# BT10_Rev2.net
KiCad netlist of a schematic drawn in EAGLE
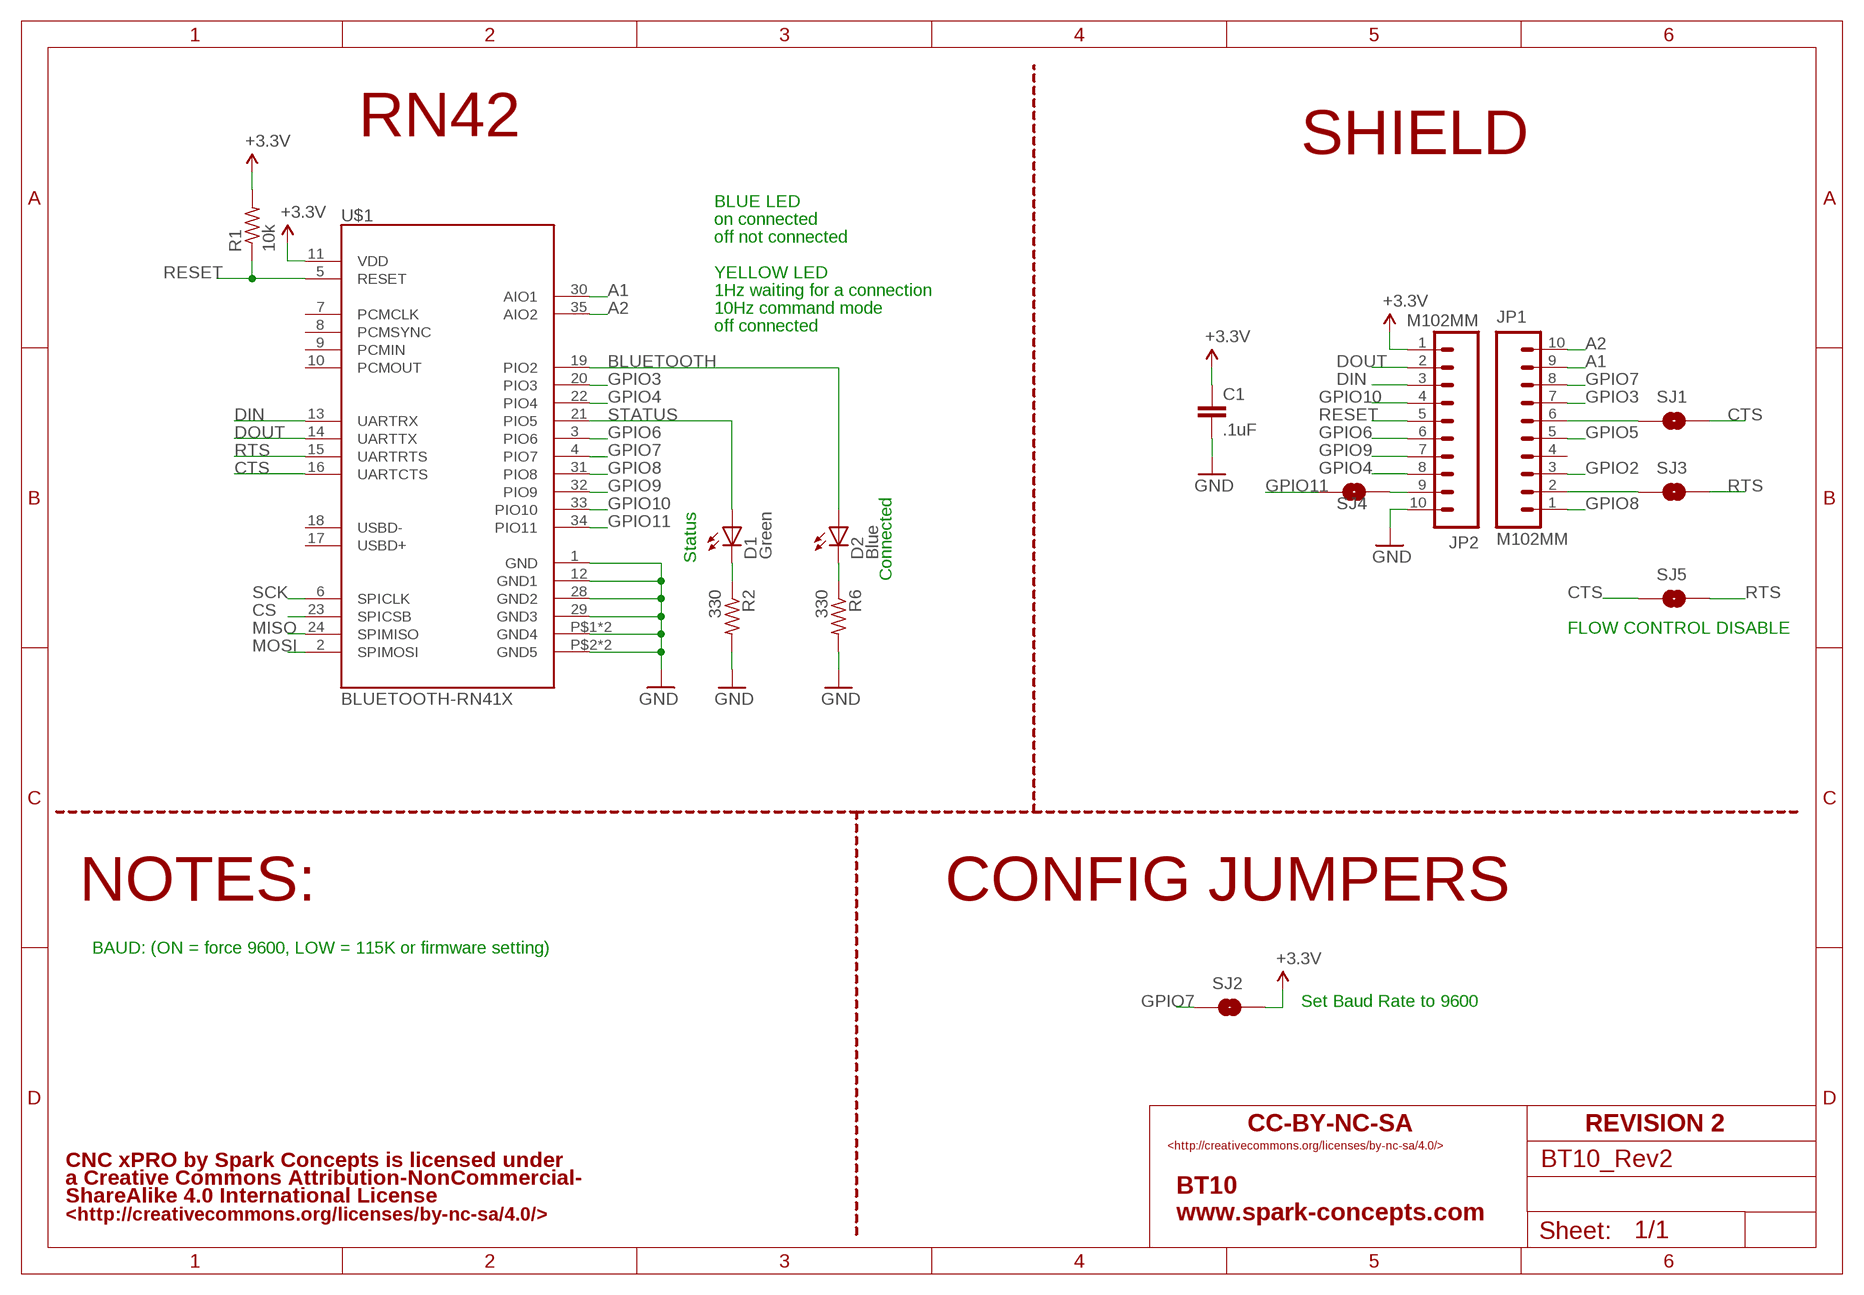
[diagram p0: schematic, sheet 1]

(export (version "E")
  (design (tool "Eeschema 10.0.6"))
  (components
    (comp (ref "C1")
      (value ".1uF")
      (footprint "eagle-import:0603-CAP")
      (libsource (lib "eagle-import") (part "CAP0603-CAP"))
    )
    (comp (ref "D1")
      (value "Green")
      (footprint "eagle-import:LED-0603")
      (libsource (lib "eagle-import") (part "LED0603"))
    )
    (comp (ref "D2")
      (value "Blue")
      (footprint "eagle-import:LED-0603")
      (libsource (lib "eagle-import") (part "LED0603"))
    )
    (comp (ref "JP1")
      (value "M102MM")
      (footprint "eagle-import:1X10-2MM")
      (libsource (lib "eagle-import") (part "M102MM"))
    )
    (comp (ref "JP2")
      (value "M102MM")
      (footprint "eagle-import:1X10-2MM")
      (libsource (lib "eagle-import") (part "M102MM"))
    )
    (comp (ref "R1")
      (value "10k")
      (footprint "eagle-import:R0603")
      (libsource (lib "eagle-import") (part "R-US_R0603"))
    )
    (comp (ref "R2")
      (value "330")
      (footprint "eagle-import:R0603")
      (libsource (lib "eagle-import") (part "R-US_R0603"))
    )
    (comp (ref "R6")
      (value "330")
      (footprint "eagle-import:R0603")
      (libsource (lib "eagle-import") (part "R-US_R0603"))
    )
    (comp (ref "SJ1")
      (value "SOLDERJUMPERNO")
      (footprint "eagle-import:SJ_2S-NO")
      (libsource (lib "eagle-import") (part "SOLDERJUMPERNO"))
    )
    (comp (ref "SJ2")
      (value "SOLDERJUMPERNC2")
      (footprint "eagle-import:SJ_2S-NOTRACE")
      (libsource (lib "eagle-import") (part "SOLDERJUMPERNC2"))
    )
    (comp (ref "SJ3")
      (value "SOLDERJUMPERNO")
      (footprint "eagle-import:SJ_2S-NO")
      (libsource (lib "eagle-import") (part "SOLDERJUMPERNO"))
    )
    (comp (ref "SJ4")
      (value "SOLDERJUMPERNO")
      (footprint "eagle-import:SJ_2S-NO")
      (libsource (lib "eagle-import") (part "SOLDERJUMPERNO"))
    )
    (comp (ref "SJ5")
      (value "SOLDERJUMPERNC2")
      (footprint "eagle-import:SJ_2S-NOTRACE")
      (libsource (lib "eagle-import") (part "SOLDERJUMPERNC2"))
    )
    (comp (ref "U$1")
      (value "BLUETOOTH-RN41X")
      (footprint "eagle-import:RN41_NO_ANT")
      (libsource (lib "eagle-import") (part "BLUETOOTH-RN41X"))
    )
  )
  (nets
    (net (code "1") (name "+3.3V") (class "Default")
      (node (ref "C1") (pin "1") (pinfunction "1_1") (pintype "passive"))
      (node (ref "JP2") (pin "1") (pinfunction "1_1") (pintype "passive"))
      (node (ref "R1") (pin "2") (pinfunction "2_2") (pintype "passive"))
      (node (ref "SJ2") (pin "2") (pinfunction "2_2") (pintype "passive"))
      (node (ref "U$1") (pin "11") (pinfunction "VDD_11") (pintype "bidirectional"))
    )
    (net (code "2") (name "/A1") (class "Default")
      (node (ref "JP1") (pin "9") (pinfunction "9_9") (pintype "passive"))
      (node (ref "U$1") (pin "30") (pinfunction "AIO1_30") (pintype "bidirectional"))
    )
    (net (code "3") (name "/A2") (class "Default")
      (node (ref "JP1") (pin "10") (pinfunction "10_10") (pintype "passive"))
      (node (ref "U$1") (pin "35") (pinfunction "AIO2_35") (pintype "bidirectional"))
    )
    (net (code "4") (name "/BLUETOOTH") (class "Default")
      (node (ref "D2") (pin "A") (pinfunction "A_A") (pintype "passive"))
      (node (ref "U$1") (pin "19") (pinfunction "PIO2_19") (pintype "bidirectional"))
    )
    (net (code "5") (name "/CS") (class "Default")
      (node (ref "U$1") (pin "23") (pinfunction "SPICSB_23") (pintype "bidirectional"))
    )
    (net (code "6") (name "/CTS") (class "Default")
      (node (ref "SJ1") (pin "2") (pinfunction "2_2") (pintype "passive"))
      (node (ref "SJ5") (pin "1") (pinfunction "1_1") (pintype "passive"))
      (node (ref "U$1") (pin "16") (pinfunction "UARTCTS_16") (pintype "bidirectional"))
    )
    (net (code "7") (name "/DIN") (class "Default")
      (node (ref "JP2") (pin "3") (pinfunction "3_3") (pintype "passive"))
      (node (ref "U$1") (pin "13") (pinfunction "UARTRX_13") (pintype "bidirectional"))
    )
    (net (code "8") (name "/DOUT") (class "Default")
      (node (ref "JP2") (pin "2") (pinfunction "2_2") (pintype "passive"))
      (node (ref "U$1") (pin "14") (pinfunction "UARTTX_14") (pintype "bidirectional"))
    )
    (net (code "9") (name "/GPIO2") (class "Default")
      (node (ref "JP1") (pin "3") (pinfunction "3_3") (pintype "passive"))
    )
    (net (code "10") (name "/GPIO3") (class "Default")
      (node (ref "JP1") (pin "7") (pinfunction "7_7") (pintype "passive"))
      (node (ref "U$1") (pin "20") (pinfunction "PIO3_20") (pintype "bidirectional"))
    )
    (net (code "11") (name "/GPIO4") (class "Default")
      (node (ref "JP2") (pin "8") (pinfunction "8_8") (pintype "passive"))
      (node (ref "U$1") (pin "22") (pinfunction "PIO4_22") (pintype "bidirectional"))
    )
    (net (code "12") (name "/GPIO5") (class "Default")
      (node (ref "JP1") (pin "5") (pinfunction "5_5") (pintype "passive"))
    )
    (net (code "13") (name "/GPIO6") (class "Default")
      (node (ref "JP2") (pin "6") (pinfunction "6_6") (pintype "passive"))
      (node (ref "U$1") (pin "3") (pinfunction "PIO6_3") (pintype "bidirectional"))
    )
    (net (code "14") (name "/GPIO7") (class "Default")
      (node (ref "JP1") (pin "8") (pinfunction "8_8") (pintype "passive"))
      (node (ref "SJ2") (pin "1") (pinfunction "1_1") (pintype "passive"))
      (node (ref "U$1") (pin "4") (pinfunction "PIO7_4") (pintype "bidirectional"))
    )
    (net (code "15") (name "/GPIO8") (class "Default")
      (node (ref "JP1") (pin "1") (pinfunction "1_1") (pintype "passive"))
      (node (ref "U$1") (pin "31") (pinfunction "PIO8_31") (pintype "bidirectional"))
    )
    (net (code "16") (name "/GPIO9") (class "Default")
      (node (ref "JP2") (pin "7") (pinfunction "7_7") (pintype "passive"))
      (node (ref "U$1") (pin "32") (pinfunction "PIO9_32") (pintype "bidirectional"))
    )
    (net (code "17") (name "/GPIO10") (class "Default")
      (node (ref "JP2") (pin "4") (pinfunction "4_4") (pintype "passive"))
      (node (ref "U$1") (pin "33") (pinfunction "PIO10_33") (pintype "bidirectional"))
    )
    (net (code "18") (name "/GPIO11") (class "Default")
      (node (ref "SJ4") (pin "1") (pinfunction "1_1") (pintype "passive"))
      (node (ref "U$1") (pin "34") (pinfunction "PIO11_34") (pintype "bidirectional"))
    )
    (net (code "19") (name "/MISO") (class "Default")
      (node (ref "U$1") (pin "24") (pinfunction "SPIMISO_24") (pintype "bidirectional"))
    )
    (net (code "20") (name "/MOSI") (class "Default")
      (node (ref "U$1") (pin "2") (pinfunction "SPIMOSI_2") (pintype "bidirectional"))
    )
    (net (code "21") (name "/RESET") (class "Default")
      (node (ref "JP2") (pin "5") (pinfunction "5_5") (pintype "passive"))
      (node (ref "R1") (pin "1") (pinfunction "1_1") (pintype "passive"))
      (node (ref "U$1") (pin "5") (pinfunction "RESET_5") (pintype "bidirectional"))
    )
    (net (code "22") (name "/RTS") (class "Default")
      (node (ref "SJ3") (pin "2") (pinfunction "2_2") (pintype "passive"))
      (node (ref "SJ5") (pin "2") (pinfunction "2_2") (pintype "passive"))
      (node (ref "U$1") (pin "15") (pinfunction "UARTRTS_15") (pintype "bidirectional"))
    )
    (net (code "23") (name "/SCK") (class "Default")
      (node (ref "U$1") (pin "6") (pinfunction "SPICLK_6") (pintype "bidirectional"))
    )
    (net (code "24") (name "/STATUS") (class "Default")
      (node (ref "D1") (pin "A") (pinfunction "A_A") (pintype "passive"))
      (node (ref "U$1") (pin "21") (pinfunction "PIO5_21") (pintype "bidirectional"))
    )
    (net (code "25") (name "GND") (class "Default")
      (node (ref "C1") (pin "2") (pinfunction "2_2") (pintype "passive"))
      (node (ref "JP2") (pin "10") (pinfunction "10_10") (pintype "passive"))
      (node (ref "R2") (pin "2") (pinfunction "2_2") (pintype "passive"))
      (node (ref "R6") (pin "2") (pinfunction "2_2") (pintype "passive"))
      (node (ref "U$1") (pin "1") (pinfunction "GND_1") (pintype "bidirectional"))
      (node (ref "U$1") (pin "12") (pinfunction "GND1_12") (pintype "bidirectional"))
      (node (ref "U$1") (pin "28") (pinfunction "GND2_28") (pintype "bidirectional"))
      (node (ref "U$1") (pin "29") (pinfunction "GND3_29") (pintype "bidirectional"))
      (node (ref "U$1") (pin "P$1") (pinfunction "GND4_P$1") (pintype "bidirectional"))
      (node (ref "U$1") (pin "P$2") (pinfunction "GND5_P$2") (pintype "bidirectional"))
      (node (ref "U$1") (pin "P$3") (pinfunction "GND5_P$3") (pintype "bidirectional"))
      (node (ref "U$1") (pin "P$4") (pinfunction "GND4_P$4") (pintype "bidirectional"))
    )
    (net (code "26") (name "Net-(D1-PadC)") (class "Default")
      (node (ref "D1") (pin "C") (pinfunction "C_C") (pintype "passive"))
      (node (ref "R2") (pin "1") (pinfunction "1_1") (pintype "passive"))
    )
    (net (code "27") (name "Net-(D2-PadC)") (class "Default")
      (node (ref "D2") (pin "C") (pinfunction "C_C") (pintype "passive"))
      (node (ref "R6") (pin "1") (pinfunction "1_1") (pintype "passive"))
    )
    (net (code "28") (name "Net-(JP1-Pad2)") (class "Default")
      (node (ref "JP1") (pin "2") (pinfunction "2_2") (pintype "passive"))
      (node (ref "SJ3") (pin "1") (pinfunction "1_1") (pintype "passive"))
    )
    (net (code "29") (name "Net-(JP1-Pad6)") (class "Default")
      (node (ref "JP1") (pin "6") (pinfunction "6_6") (pintype "passive"))
      (node (ref "SJ1") (pin "1") (pinfunction "1_1") (pintype "passive"))
    )
    (net (code "30") (name "Net-(JP2-Pad9)") (class "Default")
      (node (ref "JP2") (pin "9") (pinfunction "9_9") (pintype "passive"))
      (node (ref "SJ4") (pin "2") (pinfunction "2_2") (pintype "passive"))
    )
    (net (code "31") (name "unconnected-(JP1-Pad4)") (class "Default")
      (node (ref "JP1") (pin "4") (pinfunction "4_4") (pintype "passive"))
    )
    (net (code "32") (name "unconnected-(U$1-PCMCLK-Pad7)") (class "Default")
      (node (ref "U$1") (pin "7") (pinfunction "PCMCLK_7") (pintype "bidirectional"))
    )
    (net (code "33") (name "unconnected-(U$1-PCMIN-Pad9)") (class "Default")
      (node (ref "U$1") (pin "9") (pinfunction "PCMIN_9") (pintype "bidirectional"))
    )
    (net (code "34") (name "unconnected-(U$1-PCMOUT-Pad10)") (class "Default")
      (node (ref "U$1") (pin "10") (pinfunction "PCMOUT_10") (pintype "bidirectional"))
    )
    (net (code "35") (name "unconnected-(U$1-PCMSYNC-Pad8)") (class "Default")
      (node (ref "U$1") (pin "8") (pinfunction "PCMSYNC_8") (pintype "bidirectional"))
    )
    (net (code "36") (name "unconnected-(U$1-USBD+-Pad17)") (class "Default")
      (node (ref "U$1") (pin "17") (pinfunction "USBD+_17") (pintype "bidirectional"))
    )
    (net (code "37") (name "unconnected-(U$1-USBD--Pad18)") (class "Default")
      (node (ref "U$1") (pin "18") (pinfunction "USBD-_18") (pintype "bidirectional"))
    )
  )
)
